# untitled2-6-1.net
KiCad netlist of a schematic drawn in EAGLE
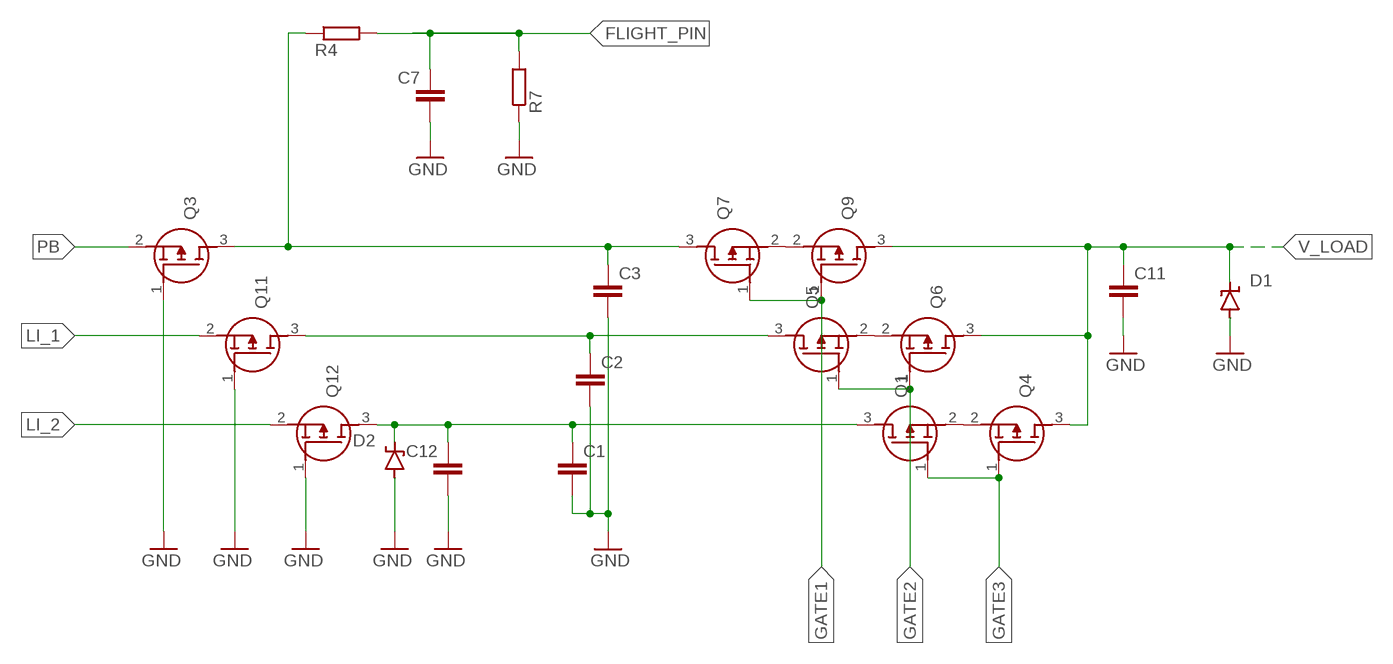
[diagram p0: schematic, sheet 1]

(export (version "E")
  (design (tool "Eeschema 10.0.6"))
  (components
    (comp (ref "C1")
      (value "100E-9F")
      (footprint "eagle-import:C0805")
      (libsource (lib "eagle-import") (part "C-EUC0805"))
    )
    (comp (ref "C2")
      (value "100E-9F")
      (footprint "eagle-import:C0805")
      (libsource (lib "eagle-import") (part "C-EUC0805"))
    )
    (comp (ref "C3")
      (value "100E-9F")
      (footprint "eagle-import:C0805")
      (libsource (lib "eagle-import") (part "C-EUC0805"))
    )
    (comp (ref "C7")
      (value "100E-9F")
      (footprint "eagle-import:C0805")
      (libsource (lib "eagle-import") (part "C-EUC0805"))
    )
    (comp (ref "C11")
      (value "100E-6F")
      (footprint "eagle-import:C0805")
      (libsource (lib "eagle-import") (part "C-EUC0805"))
    )
    (comp (ref "C12")
      (value "100E-9F")
      (footprint "eagle-import:C0805")
      (libsource (lib "eagle-import") (part "C-EUC0805"))
    )
    (comp (ref "D1")
      (value "SUPPRESSOR-SMBJ")
      (footprint "eagle-import:SMBJ")
      (libsource (lib "eagle-import") (part "SUPPRESSOR-SMBJ"))
    )
    (comp (ref "D2")
      (value "SUPPRESSOR-SMBJ")
      (footprint "eagle-import:SMBJ")
      (libsource (lib "eagle-import") (part "SUPPRESSOR-SMBJ"))
    )
    (comp (ref "Q1")
      (value "SSM3J332R,LF")
      (footprint "eagle-import:2-3Z1S(SOT-23F)")
      (fields (field (name "MOUSER_PART_NUMBER") "757-SSM3J332RLF"))
      (libsource (lib "eagle-import") (part "SSM3J332R,LF"))
    )
    (comp (ref "Q3")
      (value "SSM3J332R,LF")
      (footprint "eagle-import:2-3Z1S(SOT-23F)")
      (fields (field (name "MOUSER_PART_NUMBER") "757-SSM3J332RLF"))
      (libsource (lib "eagle-import") (part "SSM3J332R,LF"))
    )
    (comp (ref "Q4")
      (value "SSM3J332R,LF")
      (footprint "eagle-import:2-3Z1S(SOT-23F)")
      (fields (field (name "MOUSER_PART_NUMBER") "757-SSM3J332RLF"))
      (libsource (lib "eagle-import") (part "SSM3J332R,LF"))
    )
    (comp (ref "Q5")
      (value "SSM3J332R,LF")
      (footprint "eagle-import:2-3Z1S(SOT-23F)")
      (fields (field (name "MOUSER_PART_NUMBER") "757-SSM3J332RLF"))
      (libsource (lib "eagle-import") (part "SSM3J332R,LF"))
    )
    (comp (ref "Q6")
      (value "SSM3J332R,LF")
      (footprint "eagle-import:2-3Z1S(SOT-23F)")
      (fields (field (name "MOUSER_PART_NUMBER") "757-SSM3J332RLF"))
      (libsource (lib "eagle-import") (part "SSM3J332R,LF"))
    )
    (comp (ref "Q7")
      (value "SSM3J332R,LF")
      (footprint "eagle-import:2-3Z1S(SOT-23F)")
      (fields (field (name "MOUSER_PART_NUMBER") "757-SSM3J332RLF"))
      (libsource (lib "eagle-import") (part "SSM3J332R,LF"))
    )
    (comp (ref "Q9")
      (value "SSM3J332R,LF")
      (footprint "eagle-import:2-3Z1S(SOT-23F)")
      (fields (field (name "MOUSER_PART_NUMBER") "757-SSM3J332RLF"))
      (libsource (lib "eagle-import") (part "SSM3J332R,LF"))
    )
    (comp (ref "Q11")
      (value "SSM3J332R,LF")
      (footprint "eagle-import:2-3Z1S(SOT-23F)")
      (fields (field (name "MOUSER_PART_NUMBER") "757-SSM3J332RLF"))
      (libsource (lib "eagle-import") (part "SSM3J332R,LF"))
    )
    (comp (ref "Q12")
      (value "SSM3J332R,LF")
      (footprint "eagle-import:2-3Z1S(SOT-23F)")
      (fields (field (name "MOUSER_PART_NUMBER") "757-SSM3J332RLF"))
      (libsource (lib "eagle-import") (part "SSM3J332R,LF"))
    )
    (comp (ref "R4")
      (value "1E2Ω")
      (footprint "eagle-import:R0603")
      (libsource (lib "eagle-import") (part "R-EU_R0603"))
    )
    (comp (ref "R7")
      (value "1E2Ω")
      (footprint "eagle-import:R0603")
      (libsource (lib "eagle-import") (part "R-EU_R0603"))
    )
  )
  (nets
    (net (code "1") (name "FLIGHT_PIN") (class "Default")
      (node (ref "C7") (pin "1") (pinfunction "1_1") (pintype "passive"))
      (node (ref "R4") (pin "2") (pinfunction "2_2") (pintype "passive"))
      (node (ref "R7") (pin "2") (pinfunction "2_2") (pintype "passive"))
    )
    (net (code "2") (name "GATE1") (class "Default")
      (node (ref "Q7") (pin "1") (pinfunction "G_1") (pintype "bidirectional"))
      (node (ref "Q9") (pin "1") (pinfunction "G_1") (pintype "bidirectional"))
    )
    (net (code "3") (name "GATE2") (class "Default")
      (node (ref "Q5") (pin "1") (pinfunction "G_1") (pintype "bidirectional"))
      (node (ref "Q6") (pin "1") (pinfunction "G_1") (pintype "bidirectional"))
    )
    (net (code "4") (name "GATE3") (class "Default")
      (node (ref "Q1") (pin "1") (pinfunction "G_1") (pintype "bidirectional"))
      (node (ref "Q4") (pin "1") (pinfunction "G_1") (pintype "bidirectional"))
    )
    (net (code "5") (name "GND") (class "Default")
      (node (ref "C1") (pin "2") (pinfunction "2_2") (pintype "passive"))
      (node (ref "C11") (pin "2") (pinfunction "2_2") (pintype "passive"))
      (node (ref "C12") (pin "2") (pinfunction "2_2") (pintype "passive"))
      (node (ref "C2") (pin "2") (pinfunction "2_2") (pintype "passive"))
      (node (ref "C3") (pin "2") (pinfunction "2_2") (pintype "passive"))
      (node (ref "C7") (pin "2") (pinfunction "2_2") (pintype "passive"))
      (node (ref "D1") (pin "A") (pinfunction "A_A") (pintype "passive"))
      (node (ref "D2") (pin "A") (pinfunction "A_A") (pintype "passive"))
      (node (ref "Q11") (pin "1") (pinfunction "G_1") (pintype "bidirectional"))
      (node (ref "Q12") (pin "1") (pinfunction "G_1") (pintype "bidirectional"))
      (node (ref "Q3") (pin "1") (pinfunction "G_1") (pintype "bidirectional"))
      (node (ref "R7") (pin "1") (pinfunction "1_1") (pintype "passive"))
    )
    (net (code "6") (name "LI_1") (class "Default")
      (node (ref "Q11") (pin "2") (pinfunction "S_2") (pintype "bidirectional"))
    )
    (net (code "7") (name "LI_2") (class "Default")
      (node (ref "Q12") (pin "2") (pinfunction "S_2") (pintype "bidirectional"))
    )
    (net (code "8") (name "Net-(Q1-D)") (class "Default")
      (node (ref "C1") (pin "1") (pinfunction "1_1") (pintype "passive"))
      (node (ref "C12") (pin "1") (pinfunction "1_1") (pintype "passive"))
      (node (ref "D2") (pin "C") (pinfunction "C_C") (pintype "passive"))
      (node (ref "Q1") (pin "3") (pinfunction "D_3") (pintype "bidirectional"))
      (node (ref "Q12") (pin "3") (pinfunction "D_3") (pintype "bidirectional"))
    )
    (net (code "9") (name "Net-(Q1-S)") (class "Default")
      (node (ref "Q1") (pin "2") (pinfunction "S_2") (pintype "bidirectional"))
      (node (ref "Q4") (pin "2") (pinfunction "S_2") (pintype "bidirectional"))
    )
    (net (code "10") (name "Net-(Q3-D)") (class "Default")
      (node (ref "C3") (pin "1") (pinfunction "1_1") (pintype "passive"))
      (node (ref "Q3") (pin "3") (pinfunction "D_3") (pintype "bidirectional"))
      (node (ref "Q7") (pin "3") (pinfunction "D_3") (pintype "bidirectional"))
      (node (ref "R4") (pin "1") (pinfunction "1_1") (pintype "passive"))
    )
    (net (code "11") (name "Net-(Q5-S)") (class "Default")
      (node (ref "Q5") (pin "2") (pinfunction "S_2") (pintype "bidirectional"))
      (node (ref "Q6") (pin "2") (pinfunction "S_2") (pintype "bidirectional"))
    )
    (net (code "12") (name "Net-(Q7-S)") (class "Default")
      (node (ref "Q7") (pin "2") (pinfunction "S_2") (pintype "bidirectional"))
      (node (ref "Q9") (pin "2") (pinfunction "S_2") (pintype "bidirectional"))
    )
    (net (code "13") (name "Net-(Q11-D)") (class "Default")
      (node (ref "C2") (pin "1") (pinfunction "1_1") (pintype "passive"))
      (node (ref "Q11") (pin "3") (pinfunction "D_3") (pintype "bidirectional"))
      (node (ref "Q5") (pin "3") (pinfunction "D_3") (pintype "bidirectional"))
    )
    (net (code "14") (name "PB") (class "Default")
      (node (ref "Q3") (pin "2") (pinfunction "S_2") (pintype "bidirectional"))
    )
    (net (code "15") (name "V_LOAD") (class "Default")
      (node (ref "C11") (pin "1") (pinfunction "1_1") (pintype "passive"))
      (node (ref "D1") (pin "C") (pinfunction "C_C") (pintype "passive"))
      (node (ref "Q4") (pin "3") (pinfunction "D_3") (pintype "bidirectional"))
      (node (ref "Q6") (pin "3") (pinfunction "D_3") (pintype "bidirectional"))
      (node (ref "Q9") (pin "3") (pinfunction "D_3") (pintype "bidirectional"))
    )
  )
)
